# 373brd.net
KiCad netlist of a schematic drawn in EAGLE
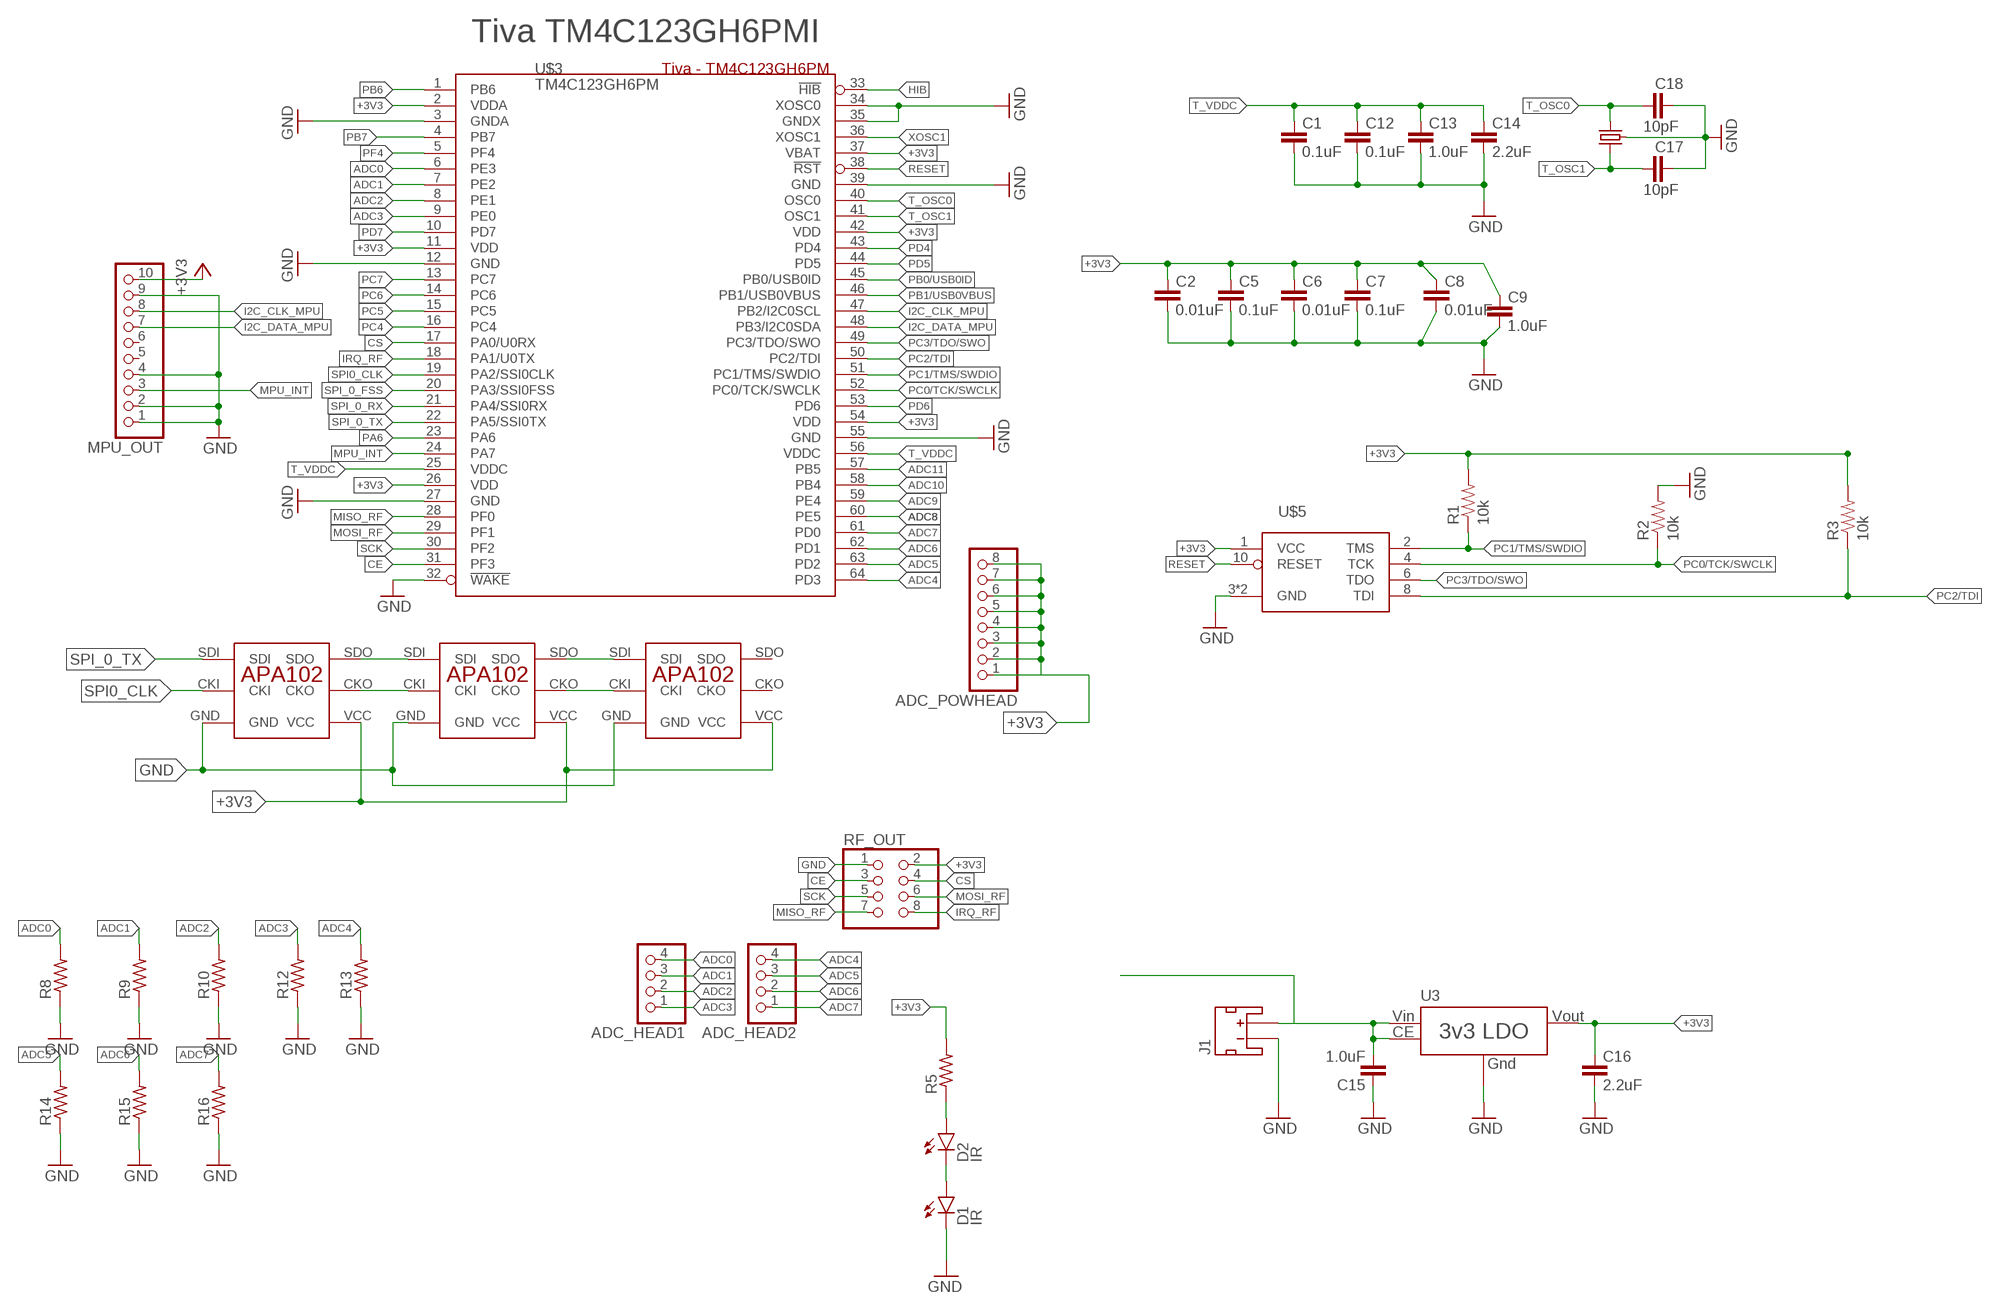
[diagram p0: schematic, sheet 1]

(export (version "E")
  (design (tool "Eeschema 10.0.6"))
  (components
    (comp (ref "ADC_HEAD1")
      (value "PINHD-1X4")
      (footprint "eagle-import:1X04")
      (libsource (lib "eagle-import") (part "PINHD-1X4"))
    )
    (comp (ref "ADC_HEAD2")
      (value "PINHD-1X4")
      (footprint "eagle-import:1X04")
      (libsource (lib "eagle-import") (part "PINHD-1X4"))
    )
    (comp (ref "ADC_POWHEAD")
      (value "PINHD-1X8")
      (footprint "eagle-import:1X08")
      (libsource (lib "eagle-import") (part "PINHD-1X8"))
    )
    (comp (ref "C1")
      (value "0.1uF")
      (footprint "eagle-import:C0603")
      (libsource (lib "eagle-import") (part "C-EUC0603"))
    )
    (comp (ref "C2")
      (value "0.01uF")
      (footprint "eagle-import:C0603")
      (libsource (lib "eagle-import") (part "C-EUC0603"))
    )
    (comp (ref "C5")
      (value "0.1uF")
      (footprint "eagle-import:C0603")
      (libsource (lib "eagle-import") (part "C-EUC0603"))
    )
    (comp (ref "C6")
      (value "0.01uF")
      (footprint "eagle-import:C0603")
      (libsource (lib "eagle-import") (part "C-EUC0603"))
    )
    (comp (ref "C7")
      (value "0.1uF")
      (footprint "eagle-import:C0603")
      (libsource (lib "eagle-import") (part "C-EUC0603"))
    )
    (comp (ref "C8")
      (value "0.01uF")
      (footprint "eagle-import:C0603")
      (libsource (lib "eagle-import") (part "C-EUC0603"))
    )
    (comp (ref "C9")
      (value "1.0uF")
      (footprint "eagle-import:C0603")
      (libsource (lib "eagle-import") (part "C-EUC0603"))
    )
    (comp (ref "C12")
      (value "0.1uF")
      (footprint "eagle-import:C0603")
      (libsource (lib "eagle-import") (part "C-EUC0603"))
    )
    (comp (ref "C13")
      (value "1.0uF")
      (footprint "eagle-import:C0603")
      (libsource (lib "eagle-import") (part "C-EUC0603"))
    )
    (comp (ref "C14")
      (value "2.2uF")
      (footprint "eagle-import:C0603")
      (libsource (lib "eagle-import") (part "C-EUC0603"))
    )
    (comp (ref "C15")
      (value "1.0uF")
      (footprint "eagle-import:C0805")
      (libsource (lib "eagle-import") (part "C-EUC0805"))
    )
    (comp (ref "C16")
      (value "2.2uF")
      (footprint "eagle-import:C0805")
      (libsource (lib "eagle-import") (part "C-EUC0805"))
    )
    (comp (ref "C17")
      (value "10pF")
      (footprint "eagle-import:C0603")
      (fields (field (name "DIGIKEY#") "399-1049-1-ND"))
      (libsource (lib "eagle-import") (part "C-EUC0603"))
    )
    (comp (ref "C18")
      (value "10pF")
      (footprint "eagle-import:C0603")
      (fields (field (name "DIGIKEY#") "399-1049-1-ND"))
      (libsource (lib "eagle-import") (part "C-EUC0603"))
    )
    (comp (ref "D1")
      (value "IR")
      (footprint "eagle-import:LED-1206")
      (libsource (lib "eagle-import") (part "LED-BLUE1206"))
    )
    (comp (ref "D2")
      (value "IR")
      (footprint "eagle-import:LED-1206")
      (libsource (lib "eagle-import") (part "LED-BLUE1206"))
    )
    (comp (ref "J1")
      (value "JST_2MM_MALE")
      (footprint "eagle-import:JST-2-SMD")
      (libsource (lib "eagle-import") (part "JST_2MM_MALE"))
    )
    (comp (ref "MPU_OUT")
      (value "PINHD-1X10")
      (footprint "eagle-import:1X10")
      (libsource (lib "eagle-import") (part "PINHD-1X10"))
    )
    (comp (ref "R1")
      (value "10k")
      (footprint "eagle-import:0603-RES")
      (libsource (lib "eagle-import") (part "RESISTOR0603-RES"))
    )
    (comp (ref "R2")
      (value "10k")
      (footprint "eagle-import:0603-RES")
      (libsource (lib "eagle-import") (part "RESISTOR0603-RES"))
    )
    (comp (ref "R3")
      (value "10k")
      (footprint "eagle-import:0603-RES")
      (libsource (lib "eagle-import") (part "RESISTOR0603-RES"))
    )
    (comp (ref "R5")
      (value "R-US_R0603")
      (footprint "eagle-import:R0603")
      (libsource (lib "eagle-import") (part "R-US_R0603"))
    )
    (comp (ref "R8")
      (value "R-US_R0603")
      (footprint "eagle-import:R0603")
      (libsource (lib "eagle-import") (part "R-US_R0603"))
    )
    (comp (ref "R9")
      (value "R-US_R0603")
      (footprint "eagle-import:R0603")
      (libsource (lib "eagle-import") (part "R-US_R0603"))
    )
    (comp (ref "R10")
      (value "R-US_R0603")
      (footprint "eagle-import:R0603")
      (libsource (lib "eagle-import") (part "R-US_R0603"))
    )
    (comp (ref "R12")
      (value "R-US_R0603")
      (footprint "eagle-import:R0603")
      (libsource (lib "eagle-import") (part "R-US_R0603"))
    )
    (comp (ref "R13")
      (value "R-US_R0603")
      (footprint "eagle-import:R0603")
      (libsource (lib "eagle-import") (part "R-US_R0603"))
    )
    (comp (ref "R14")
      (value "R-US_R0603")
      (footprint "eagle-import:R0603")
      (libsource (lib "eagle-import") (part "R-US_R0603"))
    )
    (comp (ref "R15")
      (value "R-US_R0603")
      (footprint "eagle-import:R0603")
      (libsource (lib "eagle-import") (part "R-US_R0603"))
    )
    (comp (ref "R16")
      (value "R-US_R0603")
      (footprint "eagle-import:R0603")
      (libsource (lib "eagle-import") (part "R-US_R0603"))
    )
    (comp (ref "RF_OUT")
      (value "PINHD-2X4")
      (footprint "eagle-import:2X04")
      (libsource (lib "eagle-import") (part "PINHD-2X4"))
    )
    (comp (ref "U$1")
      (value "CRYSTAL_403C11E16")
      (footprint "eagle-import:4-SMD-SWITCH")
      (libsource (lib "eagle-import") (part "CRYSTAL_403C11E16"))
    )
    (comp (ref "U$2")
      (value "APA102")
      (footprint "eagle-import:APA102")
      (libsource (lib "eagle-import") (part "APA102"))
    )
    (comp (ref "U$3")
      (value "TM4C123GH6PM")
      (footprint "eagle-import:TM4C123GH6PM")
      (libsource (lib "eagle-import") (part "TM4C123GH6PM"))
    )
    (comp (ref "U$4")
      (value "APA102")
      (footprint "eagle-import:APA102")
      (libsource (lib "eagle-import") (part "APA102"))
    )
    (comp (ref "U$5")
      (value "JTAG-ARM_TC-10")
      (footprint "eagle-import:TC2050-IDC")
      (libsource (lib "eagle-import") (part "JTAG-ARM_TC-10"))
    )
    (comp (ref "U$6")
      (value "APA102")
      (footprint "eagle-import:APA102")
      (libsource (lib "eagle-import") (part "APA102"))
    )
    (comp (ref "U3")
      (value "XC6210")
      (footprint "eagle-import:SOT-25")
      (libsource (lib "eagle-import") (part "XC6210"))
    )
  )
  (nets
    (net (code "1") (name "+3V3") (class "Default")
      (node (ref "ADC_POWHEAD") (pin "1") (pinfunction "1_1") (pintype "passive"))
      (node (ref "ADC_POWHEAD") (pin "2") (pinfunction "2_2") (pintype "passive"))
      (node (ref "ADC_POWHEAD") (pin "3") (pinfunction "3_3") (pintype "passive"))
      (node (ref "ADC_POWHEAD") (pin "4") (pinfunction "4_4") (pintype "passive"))
      (node (ref "ADC_POWHEAD") (pin "5") (pinfunction "5_5") (pintype "passive"))
      (node (ref "ADC_POWHEAD") (pin "6") (pinfunction "6_6") (pintype "passive"))
      (node (ref "ADC_POWHEAD") (pin "7") (pinfunction "7_7") (pintype "passive"))
      (node (ref "ADC_POWHEAD") (pin "8") (pinfunction "8_8") (pintype "passive"))
      (node (ref "C16") (pin "1") (pinfunction "1_1") (pintype "passive"))
      (node (ref "C2") (pin "1") (pinfunction "1_1") (pintype "passive"))
      (node (ref "C5") (pin "1") (pinfunction "1_1") (pintype "passive"))
      (node (ref "C6") (pin "1") (pinfunction "1_1") (pintype "passive"))
      (node (ref "C7") (pin "1") (pinfunction "1_1") (pintype "passive"))
      (node (ref "C8") (pin "1") (pinfunction "1_1") (pintype "passive"))
      (node (ref "C9") (pin "1") (pinfunction "1_1") (pintype "passive"))
      (node (ref "MPU_OUT") (pin "10") (pinfunction "10_10") (pintype "passive"))
      (node (ref "R1") (pin "2") (pinfunction "2_2") (pintype "passive"))
      (node (ref "R3") (pin "2") (pinfunction "2_2") (pintype "passive"))
      (node (ref "R5") (pin "2") (pinfunction "2_2") (pintype "passive"))
      (node (ref "RF_OUT") (pin "2") (pinfunction "2_2") (pintype "passive"))
      (node (ref "U$2") (pin "VCC") (pinfunction "VCC_VCC") (pintype "bidirectional"))
      (node (ref "U$3") (pin "11") (pinfunction "VDD_11") (pintype "bidirectional"))
      (node (ref "U$3") (pin "2") (pinfunction "VDDA_2") (pintype "bidirectional"))
      (node (ref "U$3") (pin "26") (pinfunction "VDD_26") (pintype "bidirectional"))
      (node (ref "U$3") (pin "37") (pinfunction "VBAT_37") (pintype "bidirectional"))
      (node (ref "U$3") (pin "42") (pinfunction "VDD_42") (pintype "bidirectional"))
      (node (ref "U$3") (pin "54") (pinfunction "VDD_54") (pintype "bidirectional"))
      (node (ref "U$4") (pin "VCC") (pinfunction "VCC_VCC") (pintype "bidirectional"))
      (node (ref "U$5") (pin "1") (pinfunction "VCC_1") (pintype "bidirectional"))
      (node (ref "U$6") (pin "VCC") (pinfunction "VCC_VCC") (pintype "bidirectional"))
      (node (ref "U3") (pin "5") (pinfunction "VOUT_5") (pintype "power_in"))
    )
    (net (code "2") (name "ADC0") (class "Default")
      (node (ref "ADC_HEAD1") (pin "4") (pinfunction "4_4") (pintype "passive"))
      (node (ref "R8") (pin "2") (pinfunction "2_2") (pintype "passive"))
      (node (ref "U$3") (pin "6") (pinfunction "PE3_6") (pintype "bidirectional"))
    )
    (net (code "3") (name "ADC1") (class "Default")
      (node (ref "ADC_HEAD1") (pin "3") (pinfunction "3_3") (pintype "passive"))
      (node (ref "R9") (pin "2") (pinfunction "2_2") (pintype "passive"))
      (node (ref "U$3") (pin "7") (pinfunction "PE2_7") (pintype "bidirectional"))
    )
    (net (code "4") (name "ADC2") (class "Default")
      (node (ref "ADC_HEAD1") (pin "2") (pinfunction "2_2") (pintype "passive"))
      (node (ref "R10") (pin "2") (pinfunction "2_2") (pintype "passive"))
      (node (ref "U$3") (pin "8") (pinfunction "PE1_8") (pintype "bidirectional"))
    )
    (net (code "5") (name "ADC3") (class "Default")
      (node (ref "ADC_HEAD1") (pin "1") (pinfunction "1_1") (pintype "passive"))
      (node (ref "R12") (pin "2") (pinfunction "2_2") (pintype "passive"))
      (node (ref "U$3") (pin "9") (pinfunction "PE0_9") (pintype "bidirectional"))
    )
    (net (code "6") (name "ADC4") (class "Default")
      (node (ref "ADC_HEAD2") (pin "4") (pinfunction "4_4") (pintype "passive"))
      (node (ref "R13") (pin "2") (pinfunction "2_2") (pintype "passive"))
      (node (ref "U$3") (pin "64") (pinfunction "PD3_64") (pintype "bidirectional"))
    )
    (net (code "7") (name "ADC5") (class "Default")
      (node (ref "ADC_HEAD2") (pin "3") (pinfunction "3_3") (pintype "passive"))
      (node (ref "R14") (pin "2") (pinfunction "2_2") (pintype "passive"))
      (node (ref "U$3") (pin "63") (pinfunction "PD2_63") (pintype "bidirectional"))
    )
    (net (code "8") (name "ADC6") (class "Default")
      (node (ref "ADC_HEAD2") (pin "2") (pinfunction "2_2") (pintype "passive"))
      (node (ref "R15") (pin "2") (pinfunction "2_2") (pintype "passive"))
      (node (ref "U$3") (pin "62") (pinfunction "PD1_62") (pintype "bidirectional"))
    )
    (net (code "9") (name "ADC7") (class "Default")
      (node (ref "ADC_HEAD2") (pin "1") (pinfunction "1_1") (pintype "passive"))
      (node (ref "R16") (pin "2") (pinfunction "2_2") (pintype "passive"))
      (node (ref "U$3") (pin "61") (pinfunction "PD0_61") (pintype "bidirectional"))
    )
    (net (code "10") (name "ADC8") (class "Default")
      (node (ref "U$3") (pin "60") (pinfunction "PE5_60") (pintype "bidirectional"))
    )
    (net (code "11") (name "ADC9") (class "Default")
      (node (ref "U$3") (pin "59") (pinfunction "PE4_59") (pintype "bidirectional"))
    )
    (net (code "12") (name "ADC10") (class "Default")
      (node (ref "U$3") (pin "58") (pinfunction "PB4_58") (pintype "bidirectional"))
    )
    (net (code "13") (name "ADC11") (class "Default")
      (node (ref "U$3") (pin "57") (pinfunction "PB5_57") (pintype "bidirectional"))
    )
    (net (code "14") (name "CE") (class "Default")
      (node (ref "RF_OUT") (pin "3") (pinfunction "3_3") (pintype "passive"))
      (node (ref "U$3") (pin "31") (pinfunction "PF3_31") (pintype "bidirectional"))
    )
    (net (code "15") (name "CS") (class "Default")
      (node (ref "RF_OUT") (pin "4") (pinfunction "4_4") (pintype "passive"))
      (node (ref "U$3") (pin "17") (pinfunction "PA0/U0RX_17") (pintype "bidirectional"))
    )
    (net (code "16") (name "GND") (class "Default")
      (node (ref "C1") (pin "2") (pinfunction "2_2") (pintype "passive"))
      (node (ref "C12") (pin "2") (pinfunction "2_2") (pintype "passive"))
      (node (ref "C13") (pin "2") (pinfunction "2_2") (pintype "passive"))
      (node (ref "C14") (pin "2") (pinfunction "2_2") (pintype "passive"))
      (node (ref "C15") (pin "1") (pinfunction "1_1") (pintype "passive"))
      (node (ref "C16") (pin "2") (pinfunction "2_2") (pintype "passive"))
      (node (ref "C17") (pin "2") (pinfunction "2_2") (pintype "passive"))
      (node (ref "C18") (pin "2") (pinfunction "2_2") (pintype "passive"))
      (node (ref "C2") (pin "2") (pinfunction "2_2") (pintype "passive"))
      (node (ref "C5") (pin "2") (pinfunction "2_2") (pintype "passive"))
      (node (ref "C6") (pin "2") (pinfunction "2_2") (pintype "passive"))
      (node (ref "C7") (pin "2") (pinfunction "2_2") (pintype "passive"))
      (node (ref "C8") (pin "2") (pinfunction "2_2") (pintype "passive"))
      (node (ref "C9") (pin "2") (pinfunction "2_2") (pintype "passive"))
      (node (ref "D1") (pin "C") (pinfunction "C_C") (pintype "passive"))
      (node (ref "J1") (pin "1") (pinfunction "-_1") (pintype "bidirectional"))
      (node (ref "MPU_OUT") (pin "1") (pinfunction "1_1") (pintype "passive"))
      (node (ref "MPU_OUT") (pin "2") (pinfunction "2_2") (pintype "passive"))
      (node (ref "MPU_OUT") (pin "4") (pinfunction "4_4") (pintype "passive"))
      (node (ref "MPU_OUT") (pin "9") (pinfunction "9_9") (pintype "passive"))
      (node (ref "R10") (pin "1") (pinfunction "1_1") (pintype "passive"))
      (node (ref "R12") (pin "1") (pinfunction "1_1") (pintype "passive"))
      (node (ref "R13") (pin "1") (pinfunction "1_1") (pintype "passive"))
      (node (ref "R14") (pin "1") (pinfunction "1_1") (pintype "passive"))
      (node (ref "R15") (pin "1") (pinfunction "1_1") (pintype "passive"))
      (node (ref "R16") (pin "1") (pinfunction "1_1") (pintype "passive"))
      (node (ref "R2") (pin "2") (pinfunction "2_2") (pintype "passive"))
      (node (ref "R8") (pin "1") (pinfunction "1_1") (pintype "passive"))
      (node (ref "R9") (pin "1") (pinfunction "1_1") (pintype "passive"))
      (node (ref "RF_OUT") (pin "1") (pinfunction "1_1") (pintype "passive"))
      (node (ref "U$1") (pin "2") (pinfunction "GND_2") (pintype "bidirectional"))
      (node (ref "U$1") (pin "4") (pinfunction "GND_4") (pintype "bidirectional"))
      (node (ref "U$2") (pin "GND") (pinfunction "GND_GND") (pintype "bidirectional"))
      (node (ref "U$3") (pin "12") (pinfunction "GND_12") (pintype "bidirectional"))
      (node (ref "U$3") (pin "27") (pinfunction "GND_27") (pintype "bidirectional"))
      (node (ref "U$3") (pin "3") (pinfunction "GNDA_3") (pintype "bidirectional"))
      (node (ref "U$3") (pin "32") (pinfunction "~{WAKE}_32") (pintype "bidirectional"))
      (node (ref "U$3") (pin "34") (pinfunction "XOSC0_34") (pintype "bidirectional"))
      (node (ref "U$3") (pin "35") (pinfunction "GNDX_35") (pintype "bidirectional"))
      (node (ref "U$3") (pin "39") (pinfunction "GND_39") (pintype "bidirectional"))
      (node (ref "U$3") (pin "55") (pinfunction "GND_55") (pintype "bidirectional"))
      (node (ref "U$4") (pin "GND") (pinfunction "GND_GND") (pintype "bidirectional"))
      (node (ref "U$5") (pin "3") (pinfunction "GND_3") (pintype "bidirectional"))
      (node (ref "U$5") (pin "9") (pinfunction "GND_9") (pintype "bidirectional"))
      (node (ref "U$6") (pin "GND") (pinfunction "GND_GND") (pintype "bidirectional"))
      (node (ref "U3") (pin "2") (pinfunction "GND_2") (pintype "power_in"))
    )
    (net (code "17") (name "HIB") (class "Default")
      (node (ref "U$3") (pin "33") (pinfunction "~{HIB}_33") (pintype "bidirectional"))
    )
    (net (code "18") (name "I2C_CLK_MPU") (class "Default")
      (node (ref "MPU_OUT") (pin "8") (pinfunction "8_8") (pintype "passive"))
      (node (ref "U$3") (pin "47") (pinfunction "PB2/I2C0SCL_47") (pintype "bidirectional"))
    )
    (net (code "19") (name "I2C_DATA_MPU") (class "Default")
      (node (ref "MPU_OUT") (pin "7") (pinfunction "7_7") (pintype "passive"))
      (node (ref "U$3") (pin "48") (pinfunction "PB3/I2C0SDA_48") (pintype "bidirectional"))
    )
    (net (code "20") (name "IRQ_RF") (class "Default")
      (node (ref "RF_OUT") (pin "8") (pinfunction "8_8") (pintype "passive"))
      (node (ref "U$3") (pin "18") (pinfunction "PA1/U0TX_18") (pintype "bidirectional"))
    )
    (net (code "21") (name "MISO_RF") (class "Default")
      (node (ref "RF_OUT") (pin "7") (pinfunction "7_7") (pintype "passive"))
      (node (ref "U$3") (pin "28") (pinfunction "PF0_28") (pintype "bidirectional"))
    )
    (net (code "22") (name "MOSI_RF") (class "Default")
      (node (ref "RF_OUT") (pin "6") (pinfunction "6_6") (pintype "passive"))
      (node (ref "U$3") (pin "29") (pinfunction "PF1_29") (pintype "bidirectional"))
    )
    (net (code "23") (name "MPU_INT") (class "Default")
      (node (ref "MPU_OUT") (pin "3") (pinfunction "3_3") (pintype "passive"))
      (node (ref "U$3") (pin "24") (pinfunction "PA7_24") (pintype "bidirectional"))
    )
    (net (code "24") (name "Net-(D1-PadA)") (class "Default")
      (node (ref "D1") (pin "A") (pinfunction "A_A") (pintype "passive"))
      (node (ref "D2") (pin "C") (pinfunction "C_C") (pintype "passive"))
    )
    (net (code "25") (name "Net-(D2-PadA)") (class "Default")
      (node (ref "D2") (pin "A") (pinfunction "A_A") (pintype "passive"))
      (node (ref "R5") (pin "1") (pinfunction "1_1") (pintype "passive"))
    )
    (net (code "26") (name "Net-(J1-+)") (class "Default")
      (node (ref "C15") (pin "2") (pinfunction "2_2") (pintype "passive"))
      (node (ref "J1") (pin "2") (pinfunction "+_2") (pintype "bidirectional"))
      (node (ref "U3") (pin "1") (pinfunction "VIN_1") (pintype "power_in"))
      (node (ref "U3") (pin "3") (pinfunction "CE_3") (pintype "input"))
    )
    (net (code "27") (name "Net-(U$2-PadCKO)") (class "Default")
      (node (ref "U$2") (pin "CKO") (pinfunction "CKO_CKO") (pintype "bidirectional"))
      (node (ref "U$4") (pin "CKI") (pinfunction "CKI_CKI") (pintype "bidirectional"))
    )
    (net (code "28") (name "Net-(U$2-PadSDO)") (class "Default")
      (node (ref "U$2") (pin "SDO") (pinfunction "SDO_SDO") (pintype "bidirectional"))
      (node (ref "U$4") (pin "SDI") (pinfunction "SDI_SDI") (pintype "bidirectional"))
    )
    (net (code "29") (name "Net-(U$4-PadCKO)") (class "Default")
      (node (ref "U$4") (pin "CKO") (pinfunction "CKO_CKO") (pintype "bidirectional"))
      (node (ref "U$6") (pin "CKI") (pinfunction "CKI_CKI") (pintype "bidirectional"))
    )
    (net (code "30") (name "Net-(U$4-PadSDO)") (class "Default")
      (node (ref "U$4") (pin "SDO") (pinfunction "SDO_SDO") (pintype "bidirectional"))
      (node (ref "U$6") (pin "SDI") (pinfunction "SDI_SDI") (pintype "bidirectional"))
    )
    (net (code "31") (name "PA6") (class "Default")
      (node (ref "U$3") (pin "23") (pinfunction "PA6_23") (pintype "bidirectional"))
    )
    (net (code "32") (name "PB0{slash}USB0ID") (class "Default")
      (node (ref "U$3") (pin "45") (pinfunction "PB0/USB0ID_45") (pintype "bidirectional"))
    )
    (net (code "33") (name "PB1{slash}USB0VBUS") (class "Default")
      (node (ref "U$3") (pin "46") (pinfunction "PB1/USB0VBUS_46") (pintype "bidirectional"))
    )
    (net (code "34") (name "PB6") (class "Default")
      (node (ref "U$3") (pin "1") (pinfunction "PB6_1") (pintype "bidirectional"))
    )
    (net (code "35") (name "PB7") (class "Default")
      (node (ref "U$3") (pin "4") (pinfunction "PB7_4") (pintype "bidirectional"))
    )
    (net (code "36") (name "PC0{slash}TCK{slash}SWCLK") (class "Default")
      (node (ref "R2") (pin "1") (pinfunction "1_1") (pintype "passive"))
      (node (ref "U$3") (pin "52") (pinfunction "PC0/TCK/SWCLK_52") (pintype "bidirectional"))
      (node (ref "U$5") (pin "4") (pinfunction "TCK_4") (pintype "bidirectional"))
    )
    (net (code "37") (name "PC1{slash}TMS{slash}SWDIO") (class "Default")
      (node (ref "R1") (pin "1") (pinfunction "1_1") (pintype "passive"))
      (node (ref "U$3") (pin "51") (pinfunction "PC1/TMS/SWDIO_51") (pintype "bidirectional"))
      (node (ref "U$5") (pin "2") (pinfunction "TMS_2") (pintype "bidirectional"))
    )
    (net (code "38") (name "PC2{slash}TDI") (class "Default")
      (node (ref "R3") (pin "1") (pinfunction "1_1") (pintype "passive"))
      (node (ref "U$3") (pin "50") (pinfunction "PC2/TDI_50") (pintype "bidirectional"))
      (node (ref "U$5") (pin "8") (pinfunction "TDI_8") (pintype "bidirectional"))
    )
    (net (code "39") (name "PC3{slash}TDO{slash}SWO") (class "Default")
      (node (ref "U$3") (pin "49") (pinfunction "PC3/TDO/SWO_49") (pintype "bidirectional"))
      (node (ref "U$5") (pin "6") (pinfunction "TDO_6") (pintype "bidirectional"))
    )
    (net (code "40") (name "PC4") (class "Default")
      (node (ref "U$3") (pin "16") (pinfunction "PC4_16") (pintype "bidirectional"))
    )
    (net (code "41") (name "PC5") (class "Default")
      (node (ref "U$3") (pin "15") (pinfunction "PC5_15") (pintype "bidirectional"))
    )
    (net (code "42") (name "PC6") (class "Default")
      (node (ref "U$3") (pin "14") (pinfunction "PC6_14") (pintype "bidirectional"))
    )
    (net (code "43") (name "PC7") (class "Default")
      (node (ref "U$3") (pin "13") (pinfunction "PC7_13") (pintype "bidirectional"))
    )
    (net (code "44") (name "PD4") (class "Default")
      (node (ref "U$3") (pin "43") (pinfunction "PD4_43") (pintype "bidirectional"))
    )
    (net (code "45") (name "PD5") (class "Default")
      (node (ref "U$3") (pin "44") (pinfunction "PD5_44") (pintype "bidirectional"))
    )
    (net (code "46") (name "PD6") (class "Default")
      (node (ref "U$3") (pin "53") (pinfunction "PD6_53") (pintype "bidirectional"))
    )
    (net (code "47") (name "PD7") (class "Default")
      (node (ref "U$3") (pin "10") (pinfunction "PD7_10") (pintype "bidirectional"))
    )
    (net (code "48") (name "PF4") (class "Default")
      (node (ref "U$3") (pin "5") (pinfunction "PF4_5") (pintype "bidirectional"))
    )
    (net (code "49") (name "RESET") (class "Default")
      (node (ref "U$3") (pin "38") (pinfunction "~{RST}_38") (pintype "bidirectional"))
      (node (ref "U$5") (pin "10") (pinfunction "RESET_10") (pintype "bidirectional"))
    )
    (net (code "50") (name "SCK") (class "Default")
      (node (ref "RF_OUT") (pin "5") (pinfunction "5_5") (pintype "passive"))
      (node (ref "U$3") (pin "30") (pinfunction "PF2_30") (pintype "bidirectional"))
    )
    (net (code "51") (name "SPI0_CLK") (class "Default")
      (node (ref "U$2") (pin "CKI") (pinfunction "CKI_CKI") (pintype "bidirectional"))
      (node (ref "U$3") (pin "19") (pinfunction "PA2/SSI0CLK_19") (pintype "bidirectional"))
    )
    (net (code "52") (name "SPI_0_FSS") (class "Default")
      (node (ref "U$3") (pin "20") (pinfunction "PA3/SSI0FSS_20") (pintype "bidirectional"))
    )
    (net (code "53") (name "SPI_0_RX") (class "Default")
      (node (ref "U$3") (pin "21") (pinfunction "PA4/SSI0RX_21") (pintype "bidirectional"))
    )
    (net (code "54") (name "SPI_0_TX") (class "Default")
      (node (ref "U$2") (pin "SDI") (pinfunction "SDI_SDI") (pintype "bidirectional"))
      (node (ref "U$3") (pin "22") (pinfunction "PA5/SSI0TX_22") (pintype "bidirectional"))
    )
    (net (code "55") (name "T_OSC0") (class "Default")
      (node (ref "C18") (pin "1") (pinfunction "1_1") (pintype "passive"))
      (node (ref "U$1") (pin "3") (pinfunction "2_3") (pintype "bidirectional"))
      (node (ref "U$3") (pin "40") (pinfunction "OSC0_40") (pintype "bidirectional"))
    )
    (net (code "56") (name "T_OSC1") (class "Default")
      (node (ref "C17") (pin "1") (pinfunction "1_1") (pintype "passive"))
      (node (ref "U$1") (pin "1") (pinfunction "1_1") (pintype "bidirectional"))
      (node (ref "U$3") (pin "41") (pinfunction "OSC1_41") (pintype "bidirectional"))
    )
    (net (code "57") (name "T_VDDC") (class "Default")
      (node (ref "C1") (pin "1") (pinfunction "1_1") (pintype "passive"))
      (node (ref "C12") (pin "1") (pinfunction "1_1") (pintype "passive"))
      (node (ref "C13") (pin "1") (pinfunction "1_1") (pintype "passive"))
      (node (ref "C14") (pin "1") (pinfunction "1_1") (pintype "passive"))
      (node (ref "U$3") (pin "25") (pinfunction "VDDC_25") (pintype "bidirectional"))
      (node (ref "U$3") (pin "56") (pinfunction "VDDC_56") (pintype "bidirectional"))
    )
    (net (code "58") (name "XOSC1") (class "Default")
      (node (ref "U$3") (pin "36") (pinfunction "XOSC1_36") (pintype "bidirectional"))
    )
    (net (code "59") (name "unconnected-(J1-PAD1-PadNC1)") (class "Default")
      (node (ref "J1") (pin "NC1") (pinfunction "PAD1_NC1") (pintype "bidirectional"))
    )
    (net (code "60") (name "unconnected-(J1-PAD2-PadNC2)") (class "Default")
      (node (ref "J1") (pin "NC2") (pinfunction "PAD2_NC2") (pintype "bidirectional"))
    )
    (net (code "61") (name "unconnected-(MPU_OUT-Pad5)") (class "Default")
      (node (ref "MPU_OUT") (pin "5") (pinfunction "5_5") (pintype "passive"))
    )
    (net (code "62") (name "unconnected-(MPU_OUT-Pad6)") (class "Default")
      (node (ref "MPU_OUT") (pin "6") (pinfunction "6_6") (pintype "passive"))
    )
    (net (code "63") (name "unconnected-(U$6-PadCKO)") (class "Default")
      (node (ref "U$6") (pin "CKO") (pinfunction "CKO_CKO") (pintype "bidirectional"))
    )
    (net (code "64") (name "unconnected-(U$6-PadSDO)") (class "Default")
      (node (ref "U$6") (pin "SDO") (pinfunction "SDO_SDO") (pintype "bidirectional"))
    )
  )
)
